# 04_Seven_Seg.net
KiCad netlist of a schematic drawn in Altium Designer
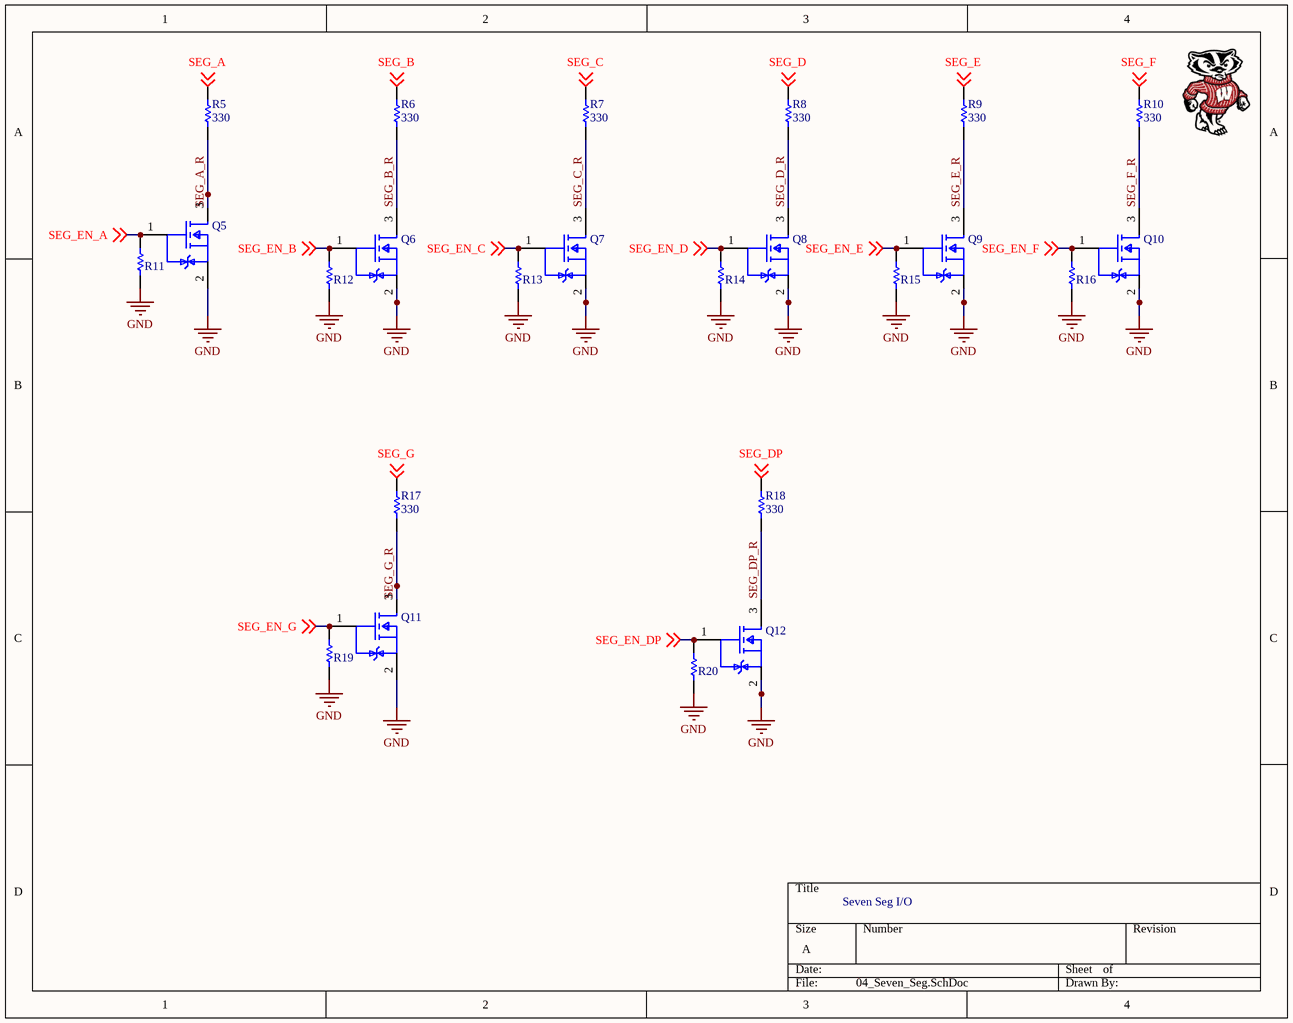
[diagram p0: 04_Seven_Seg.SchDoc]

(export (version "E")
  (design (tool "Eeschema 10.0.6"))
  (components
    (comp (ref "Q5")
      (value "SSM3K329R,LF")
      (footprint "FP-2-3Z1A-MFG")
      (description "MOSFET N CH 30V 3.5A 2-3Z1A")
      (libsource (lib "Altium Content Vault") (part "a1640d25ff429ac9f2c6fc6aeb7bb9e"))
    )
    (comp (ref "Q6")
      (value "SSM3K329R,LF")
      (footprint "FP-2-3Z1A-MFG")
      (description "MOSFET N CH 30V 3.5A 2-3Z1A")
      (libsource (lib "Altium Content Vault") (part "a1640d25ff429ac9f2c6fc6aeb7bb9e"))
    )
    (comp (ref "Q7")
      (value "SSM3K329R,LF")
      (footprint "FP-2-3Z1A-MFG")
      (description "MOSFET N CH 30V 3.5A 2-3Z1A")
      (libsource (lib "Altium Content Vault") (part "a1640d25ff429ac9f2c6fc6aeb7bb9e"))
    )
    (comp (ref "Q8")
      (value "SSM3K329R,LF")
      (footprint "FP-2-3Z1A-MFG")
      (description "MOSFET N CH 30V 3.5A 2-3Z1A")
      (libsource (lib "Altium Content Vault") (part "a1640d25ff429ac9f2c6fc6aeb7bb9e"))
    )
    (comp (ref "Q9")
      (value "SSM3K329R,LF")
      (footprint "FP-2-3Z1A-MFG")
      (description "MOSFET N CH 30V 3.5A 2-3Z1A")
      (libsource (lib "Altium Content Vault") (part "a1640d25ff429ac9f2c6fc6aeb7bb9e"))
    )
    (comp (ref "Q10")
      (value "SSM3K329R,LF")
      (footprint "FP-2-3Z1A-MFG")
      (description "MOSFET N CH 30V 3.5A 2-3Z1A")
      (libsource (lib "Altium Content Vault") (part "a1640d25ff429ac9f2c6fc6aeb7bb9e"))
    )
    (comp (ref "Q11")
      (value "SSM3K329R,LF")
      (footprint "FP-2-3Z1A-MFG")
      (description "MOSFET N CH 30V 3.5A 2-3Z1A")
      (libsource (lib "Altium Content Vault") (part "a1640d25ff429ac9f2c6fc6aeb7bb9e"))
    )
    (comp (ref "Q12")
      (value "SSM3K329R,LF")
      (footprint "FP-2-3Z1A-MFG")
      (description "MOSFET N CH 30V 3.5A 2-3Z1A")
      (libsource (lib "Altium Content Vault") (part "a1640d25ff429ac9f2c6fc6aeb7bb9e"))
    )
    (comp (ref "R5")
      (value "330")
      (footprint "RES_0805")
      (description "RES 330 OHM 1% 1/8W 0805")
      (fields (field (name "TOLERANCE") "1%"))
      (libsource (lib "team6") (part "RES_0805_R_330.00"))
    )
    (comp (ref "R6")
      (value "330")
      (footprint "RES_0805")
      (description "RES 330 OHM 1% 1/8W 0805")
      (fields (field (name "TOLERANCE") "1%"))
      (libsource (lib "team6") (part "RES_0805_R_330.00"))
    )
    (comp (ref "R7")
      (value "330")
      (footprint "RES_0805")
      (description "RES 330 OHM 1% 1/8W 0805")
      (fields (field (name "TOLERANCE") "1%"))
      (libsource (lib "team6") (part "RES_0805_R_330.00"))
    )
    (comp (ref "R8")
      (value "330")
      (footprint "RES_0805")
      (description "RES 330 OHM 1% 1/8W 0805")
      (fields (field (name "TOLERANCE") "1%"))
      (libsource (lib "team6") (part "RES_0805_R_330.00"))
    )
    (comp (ref "R9")
      (value "330")
      (footprint "RES_0805")
      (description "RES 330 OHM 1% 1/8W 0805")
      (fields (field (name "TOLERANCE") "1%"))
      (libsource (lib "team6") (part "RES_0805_R_330.00"))
    )
    (comp (ref "R10")
      (value "330")
      (footprint "RES_0805")
      (description "RES 330 OHM 1% 1/8W 0805")
      (fields (field (name "TOLERANCE") "1%"))
      (libsource (lib "team6") (part "RES_0805_R_330.00"))
    )
    (comp (ref "R11")
      (value "RES_0805_K_010.00")
      (footprint "RES_0805")
      (description "RES SMD 10K OHM 1% 1/8W 0805")
      (fields (field (name "TOLERANCE") "1%"))
      (libsource (lib "team6") (part "RES_0805_K_010.00"))
    )
    (comp (ref "R12")
      (value "RES_0805_K_010.00")
      (footprint "RES_0805")
      (description "RES SMD 10K OHM 1% 1/8W 0805")
      (fields (field (name "TOLERANCE") "1%"))
      (libsource (lib "team6") (part "RES_0805_K_010.00"))
    )
    (comp (ref "R13")
      (value "RES_0805_K_010.00")
      (footprint "RES_0805")
      (description "RES SMD 10K OHM 1% 1/8W 0805")
      (fields (field (name "TOLERANCE") "1%"))
      (libsource (lib "team6") (part "RES_0805_K_010.00"))
    )
    (comp (ref "R14")
      (value "RES_0805_K_010.00")
      (footprint "RES_0805")
      (description "RES SMD 10K OHM 1% 1/8W 0805")
      (fields (field (name "TOLERANCE") "1%"))
      (libsource (lib "team6") (part "RES_0805_K_010.00"))
    )
    (comp (ref "R15")
      (value "RES_0805_K_010.00")
      (footprint "RES_0805")
      (description "RES SMD 10K OHM 1% 1/8W 0805")
      (fields (field (name "TOLERANCE") "1%"))
      (libsource (lib "team6") (part "RES_0805_K_010.00"))
    )
    (comp (ref "R16")
      (value "RES_0805_K_010.00")
      (footprint "RES_0805")
      (description "RES SMD 10K OHM 1% 1/8W 0805")
      (fields (field (name "TOLERANCE") "1%"))
      (libsource (lib "team6") (part "RES_0805_K_010.00"))
    )
    (comp (ref "R17")
      (value "330")
      (footprint "RES_0805")
      (description "RES 330 OHM 1% 1/8W 0805")
      (fields (field (name "TOLERANCE") "1%"))
      (libsource (lib "team6") (part "RES_0805_R_330.00"))
    )
    (comp (ref "R18")
      (value "330")
      (footprint "RES_0805")
      (description "RES 330 OHM 1% 1/8W 0805")
      (fields (field (name "TOLERANCE") "1%"))
      (libsource (lib "team6") (part "RES_0805_R_330.00"))
    )
    (comp (ref "R19")
      (value "RES_0805_K_010.00")
      (footprint "RES_0805")
      (description "RES SMD 10K OHM 1% 1/8W 0805")
      (fields (field (name "TOLERANCE") "1%"))
      (libsource (lib "team6") (part "RES_0805_K_010.00"))
    )
    (comp (ref "R20")
      (value "RES_0805_K_010.00")
      (footprint "RES_0805")
      (description "RES SMD 10K OHM 1% 1/8W 0805")
      (fields (field (name "TOLERANCE") "1%"))
      (libsource (lib "team6") (part "RES_0805_K_010.00"))
    )
  )
  (nets
    (net (code "1") (name "/SEG_A_R") (class "Default")
      (node (ref "Q5") (pin "3") (pinfunction "DRAIN_3") (pintype "passive"))
      (node (ref "R5") (pin "1") (pinfunction "1_1") (pintype "passive"))
    )
    (net (code "2") (name "/SEG_B_R") (class "Default")
      (node (ref "Q6") (pin "3") (pinfunction "DRAIN_3") (pintype "passive"))
      (node (ref "R6") (pin "1") (pinfunction "1_1") (pintype "passive"))
    )
    (net (code "3") (name "/SEG_C_R") (class "Default")
      (node (ref "Q7") (pin "3") (pinfunction "DRAIN_3") (pintype "passive"))
      (node (ref "R7") (pin "1") (pinfunction "1_1") (pintype "passive"))
    )
    (net (code "4") (name "/SEG_DP_R") (class "Default")
      (node (ref "Q12") (pin "3") (pinfunction "DRAIN_3") (pintype "passive"))
      (node (ref "R18") (pin "1") (pinfunction "1_1") (pintype "passive"))
    )
    (net (code "5") (name "/SEG_D_R") (class "Default")
      (node (ref "Q8") (pin "3") (pinfunction "DRAIN_3") (pintype "passive"))
      (node (ref "R8") (pin "1") (pinfunction "1_1") (pintype "passive"))
    )
    (net (code "6") (name "/SEG_E_R") (class "Default")
      (node (ref "Q9") (pin "3") (pinfunction "DRAIN_3") (pintype "passive"))
      (node (ref "R9") (pin "1") (pinfunction "1_1") (pintype "passive"))
    )
    (net (code "7") (name "/SEG_F_R") (class "Default")
      (node (ref "Q10") (pin "3") (pinfunction "DRAIN_3") (pintype "passive"))
      (node (ref "R10") (pin "1") (pinfunction "1_1") (pintype "passive"))
    )
    (net (code "8") (name "/SEG_G_R") (class "Default")
      (node (ref "Q11") (pin "3") (pinfunction "DRAIN_3") (pintype "passive"))
      (node (ref "R17") (pin "1") (pinfunction "1_1") (pintype "passive"))
    )
    (net (code "9") (name "GND") (class "Default")
      (node (ref "Q10") (pin "2") (pinfunction "SOURCE_2") (pintype "passive"))
      (node (ref "Q11") (pin "2") (pinfunction "SOURCE_2") (pintype "passive"))
      (node (ref "Q12") (pin "2") (pinfunction "SOURCE_2") (pintype "passive"))
      (node (ref "Q5") (pin "2") (pinfunction "SOURCE_2") (pintype "passive"))
      (node (ref "Q6") (pin "2") (pinfunction "SOURCE_2") (pintype "passive"))
      (node (ref "Q7") (pin "2") (pinfunction "SOURCE_2") (pintype "passive"))
      (node (ref "Q8") (pin "2") (pinfunction "SOURCE_2") (pintype "passive"))
      (node (ref "Q9") (pin "2") (pinfunction "SOURCE_2") (pintype "passive"))
      (node (ref "R11") (pin "1") (pinfunction "1_1") (pintype "passive"))
      (node (ref "R12") (pin "1") (pinfunction "1_1") (pintype "passive"))
      (node (ref "R13") (pin "1") (pinfunction "1_1") (pintype "passive"))
      (node (ref "R14") (pin "1") (pinfunction "1_1") (pintype "passive"))
      (node (ref "R15") (pin "1") (pinfunction "1_1") (pintype "passive"))
      (node (ref "R16") (pin "1") (pinfunction "1_1") (pintype "passive"))
      (node (ref "R19") (pin "1") (pinfunction "1_1") (pintype "passive"))
      (node (ref "R20") (pin "1") (pinfunction "1_1") (pintype "passive"))
    )
    (net (code "10") (name "SEG_A") (class "Default")
      (node (ref "R5") (pin "2") (pinfunction "2_2") (pintype "passive"))
    )
    (net (code "11") (name "SEG_B") (class "Default")
      (node (ref "R6") (pin "2") (pinfunction "2_2") (pintype "passive"))
    )
    (net (code "12") (name "SEG_C") (class "Default")
      (node (ref "R7") (pin "2") (pinfunction "2_2") (pintype "passive"))
    )
    (net (code "13") (name "SEG_D") (class "Default")
      (node (ref "R8") (pin "2") (pinfunction "2_2") (pintype "passive"))
    )
    (net (code "14") (name "SEG_DP") (class "Default")
      (node (ref "R18") (pin "2") (pinfunction "2_2") (pintype "passive"))
    )
    (net (code "15") (name "SEG_E") (class "Default")
      (node (ref "R9") (pin "2") (pinfunction "2_2") (pintype "passive"))
    )
    (net (code "16") (name "SEG_EN_A") (class "Default")
      (node (ref "Q5") (pin "1") (pinfunction "GATE_1") (pintype "passive"))
      (node (ref "R11") (pin "2") (pinfunction "2_2") (pintype "passive"))
    )
    (net (code "17") (name "SEG_EN_B") (class "Default")
      (node (ref "Q6") (pin "1") (pinfunction "GATE_1") (pintype "passive"))
      (node (ref "R12") (pin "2") (pinfunction "2_2") (pintype "passive"))
    )
    (net (code "18") (name "SEG_EN_C") (class "Default")
      (node (ref "Q7") (pin "1") (pinfunction "GATE_1") (pintype "passive"))
      (node (ref "R13") (pin "2") (pinfunction "2_2") (pintype "passive"))
    )
    (net (code "19") (name "SEG_EN_D") (class "Default")
      (node (ref "Q8") (pin "1") (pinfunction "GATE_1") (pintype "passive"))
      (node (ref "R14") (pin "2") (pinfunction "2_2") (pintype "passive"))
    )
    (net (code "20") (name "SEG_EN_DP") (class "Default")
      (node (ref "Q12") (pin "1") (pinfunction "GATE_1") (pintype "passive"))
      (node (ref "R20") (pin "2") (pinfunction "2_2") (pintype "passive"))
    )
    (net (code "21") (name "SEG_EN_E") (class "Default")
      (node (ref "Q9") (pin "1") (pinfunction "GATE_1") (pintype "passive"))
      (node (ref "R15") (pin "2") (pinfunction "2_2") (pintype "passive"))
    )
    (net (code "22") (name "SEG_EN_F") (class "Default")
      (node (ref "Q10") (pin "1") (pinfunction "GATE_1") (pintype "passive"))
      (node (ref "R16") (pin "2") (pinfunction "2_2") (pintype "passive"))
    )
    (net (code "23") (name "SEG_EN_G") (class "Default")
      (node (ref "Q11") (pin "1") (pinfunction "GATE_1") (pintype "passive"))
      (node (ref "R19") (pin "2") (pinfunction "2_2") (pintype "passive"))
    )
    (net (code "24") (name "SEG_F") (class "Default")
      (node (ref "R10") (pin "2") (pinfunction "2_2") (pintype "passive"))
    )
    (net (code "25") (name "SEG_G") (class "Default")
      (node (ref "R17") (pin "2") (pinfunction "2_2") (pintype "passive"))
    )
  )
)
